# rf_conn.net
KiCad netlist of a schematic drawn in Altium Designer
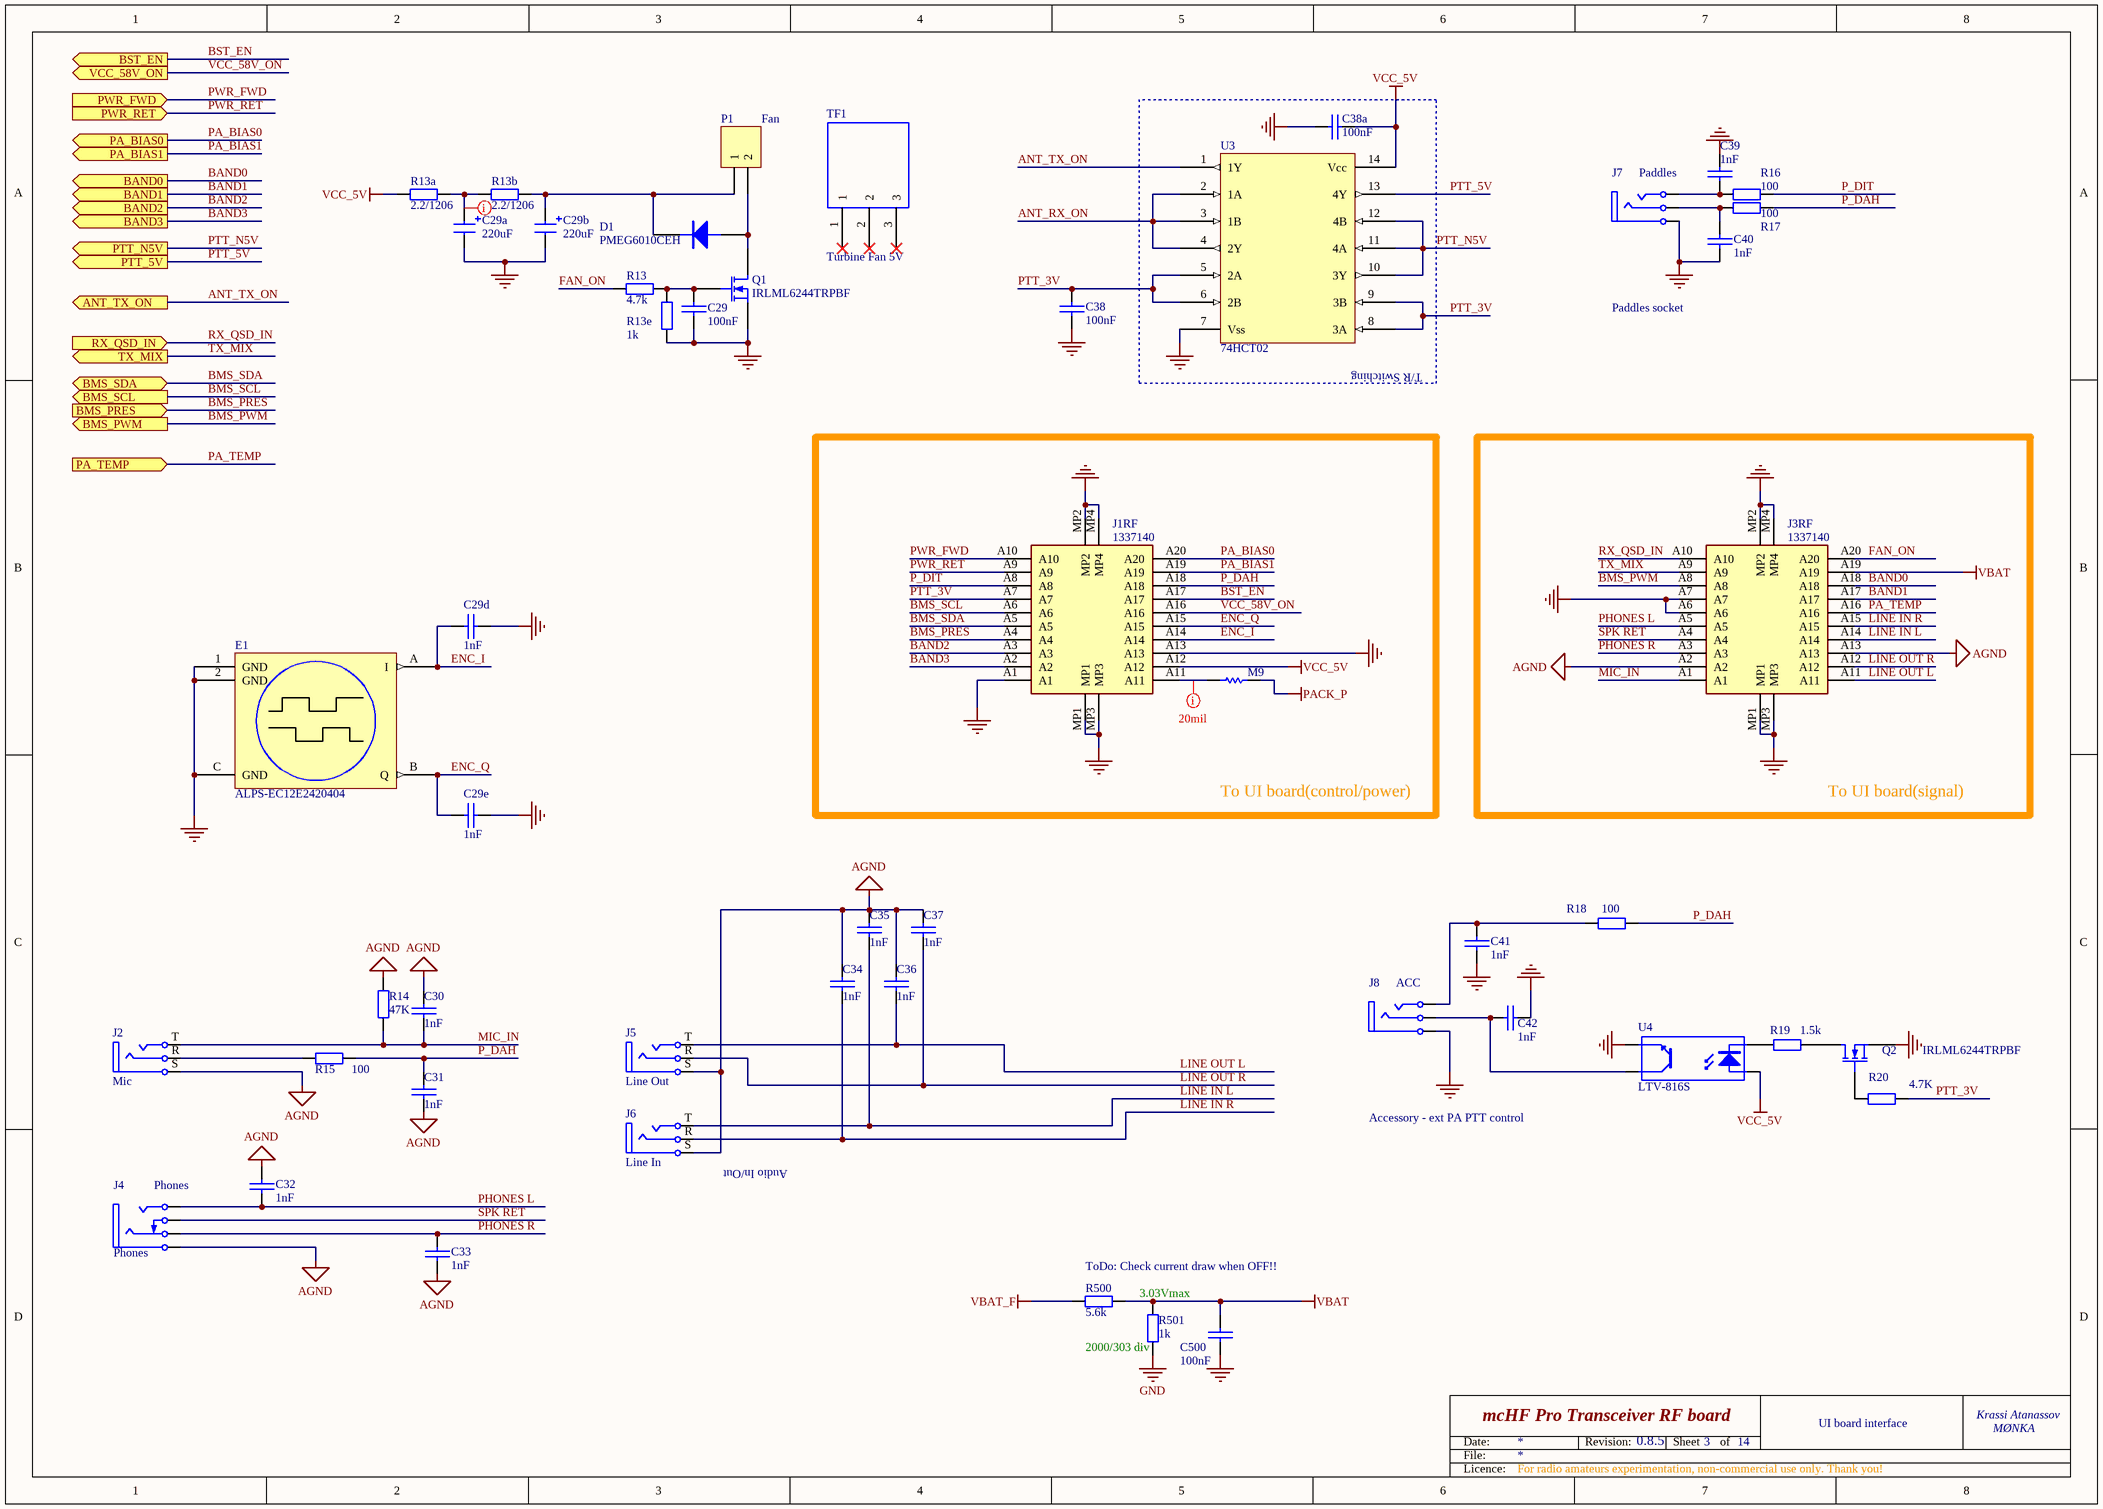
[diagram p0: rf_conn.SchDoc]

(export (version "E")
  (design (tool "Eeschema 10.0.6"))
  (components
    (comp (ref "C29")
      (value "100nF")
      (footprint "0805")
      (description "Capacitor")
      (libsource (lib "mcHF_ui") (part "CAP"))
    )
    (comp (ref "C29a")
      (value "220uF")
      (footprint "CAP_ALUM_Pro")
      (description "Electrolitic capacitor")
      (libsource (lib "mcHF_ui") (part "CAP-POL"))
    )
    (comp (ref "C29b")
      (value "220uF")
      (footprint "CAP_ALUM_Pro")
      (description "Electrolitic capacitor")
      (libsource (lib "mcHF_ui") (part "CAP-POL"))
    )
    (comp (ref "C29d")
      (value "1nF")
      (footprint "0805")
      (description "Capacitor")
      (libsource (lib "mcHF_ui") (part "CAP"))
    )
    (comp (ref "C29e")
      (value "1nF")
      (footprint "0805")
      (description "Capacitor")
      (libsource (lib "mcHF_ui") (part "CAP"))
    )
    (comp (ref "C30")
      (value "1nF")
      (footprint "0805")
      (description "Capacitor")
      (libsource (lib "mcHF_ui") (part "CAP"))
    )
    (comp (ref "C31")
      (value "1nF")
      (footprint "0805")
      (description "Capacitor")
      (libsource (lib "mcHF_ui") (part "CAP"))
    )
    (comp (ref "C32")
      (value "1nF")
      (footprint "0805")
      (description "Capacitor")
      (libsource (lib "mcHF_ui") (part "CAP"))
    )
    (comp (ref "C33")
      (value "1nF")
      (footprint "0805")
      (description "Capacitor")
      (libsource (lib "mcHF_ui") (part "CAP"))
    )
    (comp (ref "C34")
      (value "1nF")
      (footprint "0805")
      (description "Capacitor")
      (libsource (lib "mcHF_ui") (part "CAP"))
    )
    (comp (ref "C35")
      (value "1nF")
      (footprint "0805")
      (description "Capacitor")
      (libsource (lib "mcHF_ui") (part "CAP"))
    )
    (comp (ref "C36")
      (value "1nF")
      (footprint "0805")
      (description "Capacitor")
      (libsource (lib "mcHF_ui") (part "CAP"))
    )
    (comp (ref "C37")
      (value "1nF")
      (footprint "0805")
      (description "Capacitor")
      (libsource (lib "mcHF_ui") (part "CAP"))
    )
    (comp (ref "C38")
      (value "100nF")
      (footprint "0805")
      (description "Capacitor")
      (libsource (lib "mcHF_rf") (part "CAP"))
    )
    (comp (ref "C38a")
      (value "100nF")
      (footprint "0805")
      (description "Capacitor")
      (libsource (lib "mcHF_rf") (part "CAP"))
    )
    (comp (ref "C39")
      (value "1nF")
      (footprint "0805")
      (description "Capacitor")
      (libsource (lib "mcHF_rf") (part "CAP"))
    )
    (comp (ref "C40")
      (value "1nF")
      (footprint "0805")
      (description "Capacitor")
      (libsource (lib "mcHF_rf") (part "CAP"))
    )
    (comp (ref "C41")
      (value "1nF")
      (footprint "0805")
      (description "Capacitor")
      (libsource (lib "mcHF_rf") (part "CAP"))
    )
    (comp (ref "C42")
      (value "1nF")
      (footprint "0805")
      (description "Capacitor")
      (libsource (lib "mcHF_rf") (part "CAP"))
    )
    (comp (ref "C500")
      (value "100nF")
      (footprint "0805")
      (description "Capacitor")
      (libsource (lib "mcHF_rf") (part "CAP"))
    )
    (comp (ref "D1")
      (value "PMEG6010CEH")
      (footprint "SOD87")
      (description "DIODE, SCHOTTKY, 1A, 60V, SOD-123F")
      (libsource (lib "mcHF_rf") (part "PMEG6010CEH"))
    )
    (comp (ref "E1")
      (value "ALPS-EC12E2420404")
      (footprint "Encoder")
      (description "ALPS Rotary Encoder")
      (libsource (lib "__ui") (part "Encoder"))
    )
    (comp (ref "J1RF")
      (value "1337140")
      (footprint "1373866")
      (fields
        (field (name "MOUSER PART NUMBER") "651-1373866")
        (field (name "MANUFACTURER_PART_NUMBER") "1373866")
      )
      (libsource (lib "1373866") (part "1373866"))
    )
    (comp (ref "J2")
      (value "Mic")
      (footprint "MX-387GL_new1")
      (description "Jack Socket,Thru-Hole")
      (libsource (lib "mcHF_ui") (part "MX-387GL"))
    )
    (comp (ref "J3RF")
      (value "1337140")
      (footprint "1373866")
      (fields
        (field (name "MOUSER PART NUMBER") "651-1373866")
        (field (name "MANUFACTURER_PART_NUMBER") "1373866")
      )
      (libsource (lib "1373866") (part "1373866"))
    )
    (comp (ref "J4")
      (value "Phones")
      (footprint "KLBR4")
      (description "Jack Socket 4 pin")
      (fields (field (name "FUNCTION") "Phones"))
      (libsource (lib "mcHF_ui") (part "PhoneJack"))
    )
    (comp (ref "J5")
      (value "Line Out")
      (footprint "MX-387GL_new1")
      (description "Jack Socket,Thru-Hole")
      (libsource (lib "mcHF_ui") (part "MX-387GL"))
    )
    (comp (ref "J6")
      (value "Line In")
      (footprint "MX-387GL_new1")
      (description "Jack Socket,Thru-Hole")
      (libsource (lib "mcHF_ui") (part "MX-387GL"))
    )
    (comp (ref "J7")
      (value "Paddles")
      (footprint "MX-387GL_new1")
      (description "Jack Socket,Thru-Hole")
      (libsource (lib "mcHF_rf") (part "Phonejack3"))
    )
    (comp (ref "J8")
      (value "ACC")
      (footprint "MX-387GL_new1")
      (description "Jack Socket,Thru-Hole")
      (libsource (lib "mcHF_rf") (part "Phonejack3"))
    )
    (comp (ref "M9")
      (value "0")
      (footprint "SB_0603_10")
      (description "Link")
      (fields (field (name "PUBLISHER") "Altium Limited"))
      (libsource (lib "__ui") (part "Link"))
    )
    (comp (ref "P1")
      (value "Fan")
      (footprint "MHDR1X2_m")
      (description "Header, 2-Pin")
      (fields (field (name "PUBLISHER") "Altium Limited"))
      (libsource (lib "Miscellaneous Connectors") (part "MHDR1X2"))
    )
    (comp (ref "Q1")
      (value "IRLML6244TRPBF")
      (footprint "SOT-23-Pro")
      (description "N-Channel MOSFET")
      (libsource (lib "mcHF_ui_b") (part "MOSFET-N"))
    )
    (comp (ref "Q2")
      (value "IRLML6244TRPBF")
      (footprint "SOT-23-Pro")
      (description "N-Channel MOSFET")
      (libsource (lib "mcHF_ui_b") (part "MOSFET-N"))
    )
    (comp (ref "R13")
      (value "4.7k")
      (footprint "0805")
      (description "Resistor")
      (libsource (lib "") (part "RES_2"))
    )
    (comp (ref "R13a")
      (value "2.2/1206")
      (footprint "1206")
      (description "Resistor")
      (libsource (lib "mcHF_ui") (part "RES"))
    )
    (comp (ref "R13b")
      (value "2.2/1206")
      (footprint "1206")
      (description "Resistor")
      (libsource (lib "mcHF_ui") (part "RES"))
    )
    (comp (ref "R13e")
      (value "1k")
      (footprint "0805")
      (description "Resistor")
      (libsource (lib "") (part "RES_3"))
    )
    (comp (ref "R14")
      (value "47K")
      (footprint "0805")
      (description "Resistor")
      (libsource (lib "") (part "RES_1"))
    )
    (comp (ref "R15")
      (value "100")
      (footprint "0805")
      (description "Resistor")
      (libsource (lib "mcHF_ui") (part "RES"))
    )
    (comp (ref "R16")
      (value "100")
      (footprint "0805")
      (description "Resistor")
      (libsource (lib "*") (part "RES"))
    )
    (comp (ref "R17")
      (value "100")
      (footprint "0805")
      (description "Resistor")
      (libsource (lib "*") (part "RES"))
    )
    (comp (ref "R18")
      (value "100")
      (footprint "0805")
      (description "Resistor")
      (libsource (lib "*") (part "RES"))
    )
    (comp (ref "R19")
      (value "1.5k")
      (footprint "0805")
      (description "Resistor")
      (libsource (lib "mcHF_rf") (part "RES"))
    )
    (comp (ref "R20")
      (value "4.7K")
      (footprint "0805")
      (description "Resistor")
      (libsource (lib "mcHF_rf") (part "RES"))
    )
    (comp (ref "R500")
      (value "5.6k")
      (footprint "0805")
      (description "Resistor")
      (libsource (lib "mcHF_rf") (part "RES"))
    )
    (comp (ref "R501")
      (value "1k")
      (footprint "0805")
      (description "Resistor")
      (libsource (lib "") (part "RES_1"))
    )
    (comp (ref "TF1")
      (value "Turbine Fan 5V")
      (footprint "TFAN")
      (description "5V Turbine Fan, 40x40mm")
      (libsource (lib "__rf") (part "FAN5V"))
    )
    (comp (ref "U3")
      (value "74HCT02")
      (footprint "SO-14")
      (description "Quad 2-input NOR gate")
      (libsource (lib "mcHF_rf") (part "74HCT02"))
    )
    (comp (ref "U4")
      (value "LTV-816S")
      (footprint "SMDIP-4_new1")
      (description "OPTOCOUPLER, SMDIP-4, TR O/P")
      (libsource (lib "mcHF_rf") (part "ISP817XSM"))
    )
  )
  (nets
    (net (code "1") (name "/ANT_RX_ON") (class "Default")
      (node (ref "U3") (pin "2") (pinfunction "1A_2") (pintype "input"))
      (node (ref "U3") (pin "3") (pinfunction "1B_3") (pintype "input"))
      (node (ref "U3") (pin "4") (pinfunction "2Y_4") (pintype "output"))
    )
    (net (code "2") (name "/ANT_TX_ON") (class "Default")
      (node (ref "U3") (pin "1") (pinfunction "1Y_1") (pintype "output"))
    )
    (net (code "3") (name "/BAND0") (class "Default")
      (node (ref "J3RF") (pin "A18") (pinfunction "A18_A18") (pintype "passive"))
    )
    (net (code "4") (name "/BAND1") (class "Default")
      (node (ref "J3RF") (pin "A17") (pinfunction "A17_A17") (pintype "passive"))
    )
    (net (code "5") (name "/BAND2") (class "Default")
      (node (ref "J1RF") (pin "A3") (pinfunction "A3_A3") (pintype "passive"))
    )
    (net (code "6") (name "/BAND3") (class "Default")
      (node (ref "J1RF") (pin "A2") (pinfunction "A2_A2") (pintype "passive"))
    )
    (net (code "7") (name "/BMS_PRES") (class "Default")
      (node (ref "J1RF") (pin "A4") (pinfunction "A4_A4") (pintype "passive"))
    )
    (net (code "8") (name "/BMS_PWM") (class "Default")
      (node (ref "J3RF") (pin "A8") (pinfunction "A8_A8") (pintype "passive"))
    )
    (net (code "9") (name "/BMS_SCL") (class "Default")
      (node (ref "J1RF") (pin "A6") (pinfunction "A6_A6") (pintype "passive"))
    )
    (net (code "10") (name "/BMS_SDA") (class "Default")
      (node (ref "J1RF") (pin "A5") (pinfunction "A5_A5") (pintype "passive"))
    )
    (net (code "11") (name "/BST_EN") (class "Default")
      (node (ref "J1RF") (pin "A17") (pinfunction "A17_A17") (pintype "passive"))
    )
    (net (code "12") (name "/ENC_I") (class "Default")
      (node (ref "C29d") (pin "1") (pinfunction "1_1") (pintype "passive"))
      (node (ref "E1") (pin "A") (pinfunction "I_A") (pintype "output"))
      (node (ref "J1RF") (pin "A14") (pinfunction "A14_A14") (pintype "passive"))
    )
    (net (code "13") (name "/ENC_Q") (class "Default")
      (node (ref "C29e") (pin "1") (pinfunction "1_1") (pintype "passive"))
      (node (ref "E1") (pin "B") (pinfunction "Q_B") (pintype "output"))
      (node (ref "J1RF") (pin "A15") (pinfunction "A15_A15") (pintype "passive"))
    )
    (net (code "14") (name "/FAN_ON") (class "Default")
      (node (ref "J3RF") (pin "A20") (pinfunction "A20_A20") (pintype "passive"))
      (node (ref "R13") (pin "2") (pinfunction "2_2") (pintype "passive"))
    )
    (net (code "15") (name "/LINE IN L") (class "Default")
      (node (ref "C35") (pin "2") (pinfunction "2_2") (pintype "passive"))
      (node (ref "J3RF") (pin "A14") (pinfunction "A14_A14") (pintype "passive"))
      (node (ref "J6") (pin "T") (pinfunction "1_T") (pintype "passive"))
    )
    (net (code "16") (name "/LINE IN R") (class "Default")
      (node (ref "C34") (pin "2") (pinfunction "2_2") (pintype "passive"))
      (node (ref "J3RF") (pin "A15") (pinfunction "A15_A15") (pintype "passive"))
      (node (ref "J6") (pin "R") (pinfunction "3_R") (pintype "passive"))
    )
    (net (code "17") (name "/LINE OUT L") (class "Default")
      (node (ref "C36") (pin "2") (pinfunction "2_2") (pintype "passive"))
      (node (ref "J3RF") (pin "A11") (pinfunction "A11_A11") (pintype "passive"))
      (node (ref "J5") (pin "T") (pinfunction "1_T") (pintype "passive"))
    )
    (net (code "18") (name "/LINE OUT R") (class "Default")
      (node (ref "C37") (pin "2") (pinfunction "2_2") (pintype "passive"))
      (node (ref "J3RF") (pin "A12") (pinfunction "A12_A12") (pintype "passive"))
      (node (ref "J5") (pin "R") (pinfunction "3_R") (pintype "passive"))
    )
    (net (code "19") (name "/MIC_IN") (class "Default")
      (node (ref "C30") (pin "2") (pinfunction "2_2") (pintype "passive"))
      (node (ref "J2") (pin "T") (pinfunction "1_T") (pintype "passive"))
      (node (ref "J3RF") (pin "A1") (pinfunction "A1_A1") (pintype "passive"))
      (node (ref "R14") (pin "1") (pinfunction "1_1") (pintype "passive"))
    )
    (net (code "20") (name "/PA_BIAS0") (class "Default")
      (node (ref "J1RF") (pin "A20") (pinfunction "A20_A20") (pintype "passive"))
    )
    (net (code "21") (name "/PA_BIAS1") (class "Default")
      (node (ref "J1RF") (pin "A19") (pinfunction "A19_A19") (pintype "passive"))
    )
    (net (code "22") (name "/PA_TEMP") (class "Default")
      (node (ref "J3RF") (pin "A16") (pinfunction "A16_A16") (pintype "passive"))
    )
    (net (code "23") (name "/PHONES L") (class "Default")
      (node (ref "C32") (pin "1") (pinfunction "1_1") (pintype "passive"))
      (node (ref "J3RF") (pin "A5") (pinfunction "A5_A5") (pintype "passive"))
      (node (ref "J4") (pin "T") (pinfunction "T_T") (pintype "passive"))
    )
    (net (code "24") (name "/PHONES R") (class "Default")
      (node (ref "C33") (pin "2") (pinfunction "2_2") (pintype "passive"))
      (node (ref "J3RF") (pin "A3") (pinfunction "A3_A3") (pintype "passive"))
      (node (ref "J4") (pin "R") (pinfunction "R_R") (pintype "passive"))
    )
    (net (code "25") (name "/PTT_3V") (class "Default")
      (node (ref "C38") (pin "1") (pinfunction "1_1") (pintype "passive"))
      (node (ref "J1RF") (pin "A7") (pinfunction "A7_A7") (pintype "passive"))
      (node (ref "R20") (pin "2") (pinfunction "2_2") (pintype "passive"))
      (node (ref "U3") (pin "5") (pinfunction "2A_5") (pintype "input"))
      (node (ref "U3") (pin "6") (pinfunction "2B_6") (pintype "input"))
      (node (ref "U3") (pin "8") (pinfunction "3A_8") (pintype "input"))
      (node (ref "U3") (pin "9") (pinfunction "3B_9") (pintype "input"))
    )
    (net (code "26") (name "/PTT_5V") (class "Default")
      (node (ref "U3") (pin "13") (pinfunction "4Y_13") (pintype "output"))
    )
    (net (code "27") (name "/PTT_N5V") (class "Default")
      (node (ref "U3") (pin "10") (pinfunction "3Y_10") (pintype "output"))
      (node (ref "U3") (pin "11") (pinfunction "4A_11") (pintype "input"))
      (node (ref "U3") (pin "12") (pinfunction "4B_12") (pintype "input"))
    )
    (net (code "28") (name "/PWR_FWD") (class "Default")
      (node (ref "J1RF") (pin "A10") (pinfunction "A10_A10") (pintype "passive"))
    )
    (net (code "29") (name "/PWR_RET") (class "Default")
      (node (ref "J1RF") (pin "A9") (pinfunction "A9_A9") (pintype "passive"))
    )
    (net (code "30") (name "/P_DAH") (class "Default")
      (node (ref "C31") (pin "1") (pinfunction "1_1") (pintype "passive"))
      (node (ref "J1RF") (pin "A18") (pinfunction "A18_A18") (pintype "passive"))
      (node (ref "R15") (pin "2") (pinfunction "2_2") (pintype "passive"))
      (node (ref "R17") (pin "1") (pinfunction "1_1") (pintype "passive"))
      (node (ref "R18") (pin "1") (pinfunction "1_1") (pintype "passive"))
    )
    (net (code "31") (name "/P_DIT") (class "Default")
      (node (ref "J1RF") (pin "A8") (pinfunction "A8_A8") (pintype "passive"))
      (node (ref "R16") (pin "1") (pinfunction "1_1") (pintype "passive"))
    )
    (net (code "32") (name "/RX_QSD_IN") (class "Default")
      (node (ref "J3RF") (pin "A10") (pinfunction "A10_A10") (pintype "passive"))
    )
    (net (code "33") (name "/SPK RET") (class "Default")
      (node (ref "J3RF") (pin "A4") (pinfunction "A4_A4") (pintype "passive"))
      (node (ref "J4") (pin "B") (pinfunction "B_B") (pintype "passive"))
    )
    (net (code "34") (name "/TX_MIX") (class "Default")
      (node (ref "J3RF") (pin "A9") (pinfunction "A9_A9") (pintype "passive"))
    )
    (net (code "35") (name "/VCC_58V_ON") (class "Default")
      (node (ref "J1RF") (pin "A16") (pinfunction "A16_A16") (pintype "passive"))
    )
    (net (code "36") (name "AGND") (class "Default")
      (node (ref "C30") (pin "1") (pinfunction "1_1") (pintype "passive"))
      (node (ref "C31") (pin "2") (pinfunction "2_2") (pintype "passive"))
      (node (ref "C32") (pin "2") (pinfunction "2_2") (pintype "passive"))
      (node (ref "C33") (pin "1") (pinfunction "1_1") (pintype "passive"))
      (node (ref "C34") (pin "1") (pinfunction "1_1") (pintype "passive"))
      (node (ref "C35") (pin "1") (pinfunction "1_1") (pintype "passive"))
      (node (ref "C36") (pin "1") (pinfunction "1_1") (pintype "passive"))
      (node (ref "C37") (pin "1") (pinfunction "1_1") (pintype "passive"))
      (node (ref "J2") (pin "S") (pinfunction "2_S") (pintype "power_in"))
      (node (ref "J3RF") (pin "A13") (pinfunction "A13_A13") (pintype "passive"))
      (node (ref "J3RF") (pin "A2") (pinfunction "A2_A2") (pintype "passive"))
      (node (ref "J4") (pin "S") (pinfunction "S_S") (pintype "power_in"))
      (node (ref "J5") (pin "S") (pinfunction "2_S") (pintype "power_in"))
      (node (ref "J6") (pin "S") (pinfunction "2_S") (pintype "power_in"))
      (node (ref "R14") (pin "2") (pinfunction "2_2") (pintype "passive"))
    )
    (net (code "37") (name "GND") (class "Default")
      (node (ref "C29") (pin "2") (pinfunction "2_2") (pintype "passive"))
      (node (ref "C29a") (pin "2") (pinfunction "2_2") (pintype "passive"))
      (node (ref "C29b") (pin "2") (pinfunction "2_2") (pintype "passive"))
      (node (ref "C29d") (pin "2") (pinfunction "2_2") (pintype "passive"))
      (node (ref "C29e") (pin "2") (pinfunction "2_2") (pintype "passive"))
      (node (ref "C38") (pin "2") (pinfunction "2_2") (pintype "passive"))
      (node (ref "C38a") (pin "2") (pinfunction "2_2") (pintype "passive"))
      (node (ref "C39") (pin "2") (pinfunction "2_2") (pintype "passive"))
      (node (ref "C40") (pin "1") (pinfunction "1_1") (pintype "passive"))
      (node (ref "C41") (pin "2") (pinfunction "2_2") (pintype "passive"))
      (node (ref "C42") (pin "1") (pinfunction "1_1") (pintype "passive"))
      (node (ref "C500") (pin "2") (pinfunction "2_2") (pintype "passive"))
      (node (ref "E1") (pin "1") (pinfunction "GND_1") (pintype "power_in"))
      (node (ref "E1") (pin "2") (pinfunction "GND_2") (pintype "power_in"))
      (node (ref "E1") (pin "C") (pinfunction "GND_C") (pintype "power_in"))
      (node (ref "J1RF") (pin "A1") (pinfunction "A1_A1") (pintype "passive"))
      (node (ref "J1RF") (pin "A13") (pinfunction "A13_A13") (pintype "passive"))
      (node (ref "J1RF") (pin "MP1") (pinfunction "MP1_MP1") (pintype "passive"))
      (node (ref "J1RF") (pin "MP2") (pinfunction "MP2_MP2") (pintype "passive"))
      (node (ref "J1RF") (pin "MP3") (pinfunction "MP3_MP3") (pintype "passive"))
      (node (ref "J1RF") (pin "MP4") (pinfunction "MP4_MP4") (pintype "passive"))
      (node (ref "J3RF") (pin "A6") (pinfunction "A6_A6") (pintype "passive"))
      (node (ref "J3RF") (pin "A7") (pinfunction "A7_A7") (pintype "passive"))
      (node (ref "J3RF") (pin "MP1") (pinfunction "MP1_MP1") (pintype "passive"))
      (node (ref "J3RF") (pin "MP2") (pinfunction "MP2_MP2") (pintype "passive"))
      (node (ref "J3RF") (pin "MP3") (pinfunction "MP3_MP3") (pintype "passive"))
      (node (ref "J3RF") (pin "MP4") (pinfunction "MP4_MP4") (pintype "passive"))
      (node (ref "J7") (pin "S") (pinfunction "S_S") (pintype "power_in"))
      (node (ref "J8") (pin "S") (pinfunction "S_S") (pintype "power_in"))
      (node (ref "Q1") (pin "2") (pinfunction "S_2") (pintype "passive"))
      (node (ref "Q2") (pin "2") (pinfunction "S_2") (pintype "passive"))
      (node (ref "R13e") (pin "2") (pinfunction "2_2") (pintype "passive"))
      (node (ref "R501") (pin "2") (pinfunction "2_2") (pintype "passive"))
      (node (ref "U3") (pin "7") (pinfunction "Vss_7") (pintype "power_in"))
      (node (ref "U4") (pin "3") (pinfunction "E_3") (pintype "passive"))
    )
    (net (code "38") (name "Net-(C29a-Pad1)") (class "Default")
      (node (ref "C29a") (pin "1") (pinfunction "1_1") (pintype "passive"))
      (node (ref "R13a") (pin "2") (pinfunction "2_2") (pintype "passive"))
      (node (ref "R13b") (pin "1") (pinfunction "1_1") (pintype "passive"))
    )
    (net (code "39") (name "Net-(C39-Pad1)") (class "Default")
      (node (ref "C39") (pin "1") (pinfunction "1_1") (pintype "passive"))
      (node (ref "J7") (pin "T") (pinfunction "T_T") (pintype "passive"))
      (node (ref "R16") (pin "2") (pinfunction "2_2") (pintype "passive"))
    )
    (net (code "40") (name "Net-(C40-Pad2)") (class "Default")
      (node (ref "C40") (pin "2") (pinfunction "2_2") (pintype "passive"))
      (node (ref "J7") (pin "R") (pinfunction "R_R") (pintype "passive"))
      (node (ref "R17") (pin "2") (pinfunction "2_2") (pintype "passive"))
    )
    (net (code "41") (name "Net-(C41-Pad1)") (class "Default")
      (node (ref "C41") (pin "1") (pinfunction "1_1") (pintype "passive"))
      (node (ref "J8") (pin "T") (pinfunction "T_T") (pintype "passive"))
      (node (ref "R18") (pin "2") (pinfunction "2_2") (pintype "passive"))
    )
    (net (code "42") (name "Net-(D1-A)") (class "Default")
      (node (ref "D1") (pin "1") (pinfunction "A_1") (pintype "passive"))
      (node (ref "P1") (pin "2") (pinfunction "2_2") (pintype "passive"))
      (node (ref "Q1") (pin "3") (pinfunction "D_3") (pintype "passive"))
    )
    (net (code "43") (name "Net-(D1-K)") (class "Default")
      (node (ref "C29b") (pin "1") (pinfunction "1_1") (pintype "passive"))
      (node (ref "D1") (pin "2") (pinfunction "K_2") (pintype "passive"))
      (node (ref "P1") (pin "1") (pinfunction "1_1") (pintype "passive"))
      (node (ref "R13b") (pin "2") (pinfunction "2_2") (pintype "passive"))
    )
    (net (code "44") (name "Net-(J1RF-PadA11)") (class "Default")
      (node (ref "J1RF") (pin "A11") (pinfunction "A11_A11") (pintype "passive"))
      (node (ref "M9") (pin "1") (pinfunction "1_1") (pintype "passive"))
    )
    (net (code "45") (name "Net-(J2-3)") (class "Default")
      (node (ref "J2") (pin "R") (pinfunction "3_R") (pintype "passive"))
      (node (ref "R15") (pin "1") (pinfunction "1_1") (pintype "passive"))
    )
    (net (code "46") (name "Net-(Q1-G)") (class "Default")
      (node (ref "C29") (pin "1") (pinfunction "1_1") (pintype "passive"))
      (node (ref "Q1") (pin "1") (pinfunction "G_1") (pintype "passive"))
      (node (ref "R13") (pin "1") (pinfunction "1_1") (pintype "passive"))
      (node (ref "R13e") (pin "1") (pinfunction "1_1") (pintype "passive"))
    )
    (net (code "47") (name "Net-(Q2-D)") (class "Default")
      (node (ref "Q2") (pin "3") (pinfunction "D_3") (pintype "passive"))
      (node (ref "R19") (pin "2") (pinfunction "2_2") (pintype "passive"))
    )
    (net (code "48") (name "Net-(Q2-G)") (class "Default")
      (node (ref "Q2") (pin "1") (pinfunction "G_1") (pintype "passive"))
      (node (ref "R20") (pin "1") (pinfunction "1_1") (pintype "passive"))
    )
    (net (code "49") (name "Net-(U4-C)") (class "Default")
      (node (ref "C42") (pin "2") (pinfunction "2_2") (pintype "passive"))
      (node (ref "J8") (pin "R") (pinfunction "R_R") (pintype "passive"))
      (node (ref "U4") (pin "4") (pinfunction "C_4") (pintype "passive"))
    )
    (net (code "50") (name "Net-(U4-K)") (class "Default")
      (node (ref "R19") (pin "1") (pinfunction "1_1") (pintype "passive"))
      (node (ref "U4") (pin "2") (pinfunction "K_2") (pintype "passive"))
    )
    (net (code "51") (name "PACK_P") (class "Default")
      (node (ref "M9") (pin "2") (pinfunction "2_2") (pintype "passive"))
    )
    (net (code "52") (name "VBAT") (class "Default")
      (node (ref "C500") (pin "1") (pinfunction "1_1") (pintype "passive"))
      (node (ref "J3RF") (pin "A19") (pinfunction "A19_A19") (pintype "passive"))
      (node (ref "R500") (pin "2") (pinfunction "2_2") (pintype "passive"))
      (node (ref "R501") (pin "1") (pinfunction "1_1") (pintype "passive"))
    )
    (net (code "53") (name "VBAT_F") (class "Default")
      (node (ref "R500") (pin "1") (pinfunction "1_1") (pintype "passive"))
    )
    (net (code "54") (name "VCC_5V") (class "Default")
      (node (ref "C38a") (pin "1") (pinfunction "1_1") (pintype "passive"))
      (node (ref "J1RF") (pin "A12") (pinfunction "A12_A12") (pintype "passive"))
      (node (ref "R13a") (pin "1") (pinfunction "1_1") (pintype "passive"))
      (node (ref "U3") (pin "14") (pinfunction "Vcc_14") (pintype "power_in"))
      (node (ref "U4") (pin "1") (pinfunction "A_1") (pintype "passive"))
    )
    (net (code "55") (name "unconnected-(TF1-Pad1)") (class "Default")
      (node (ref "TF1") (pin "1") (pinfunction "1_1") (pintype "passive+no_connect"))
    )
    (net (code "56") (name "unconnected-(TF1-Pad2)") (class "Default")
      (node (ref "TF1") (pin "2") (pinfunction "2_2") (pintype "passive+no_connect"))
    )
    (net (code "57") (name "unconnected-(TF1-Pad3)") (class "Default")
      (node (ref "TF1") (pin "3") (pinfunction "3_3") (pintype "passive+no_connect"))
    )
  )
)
